# TTL.net
KiCad netlist of a schematic drawn in EAGLE
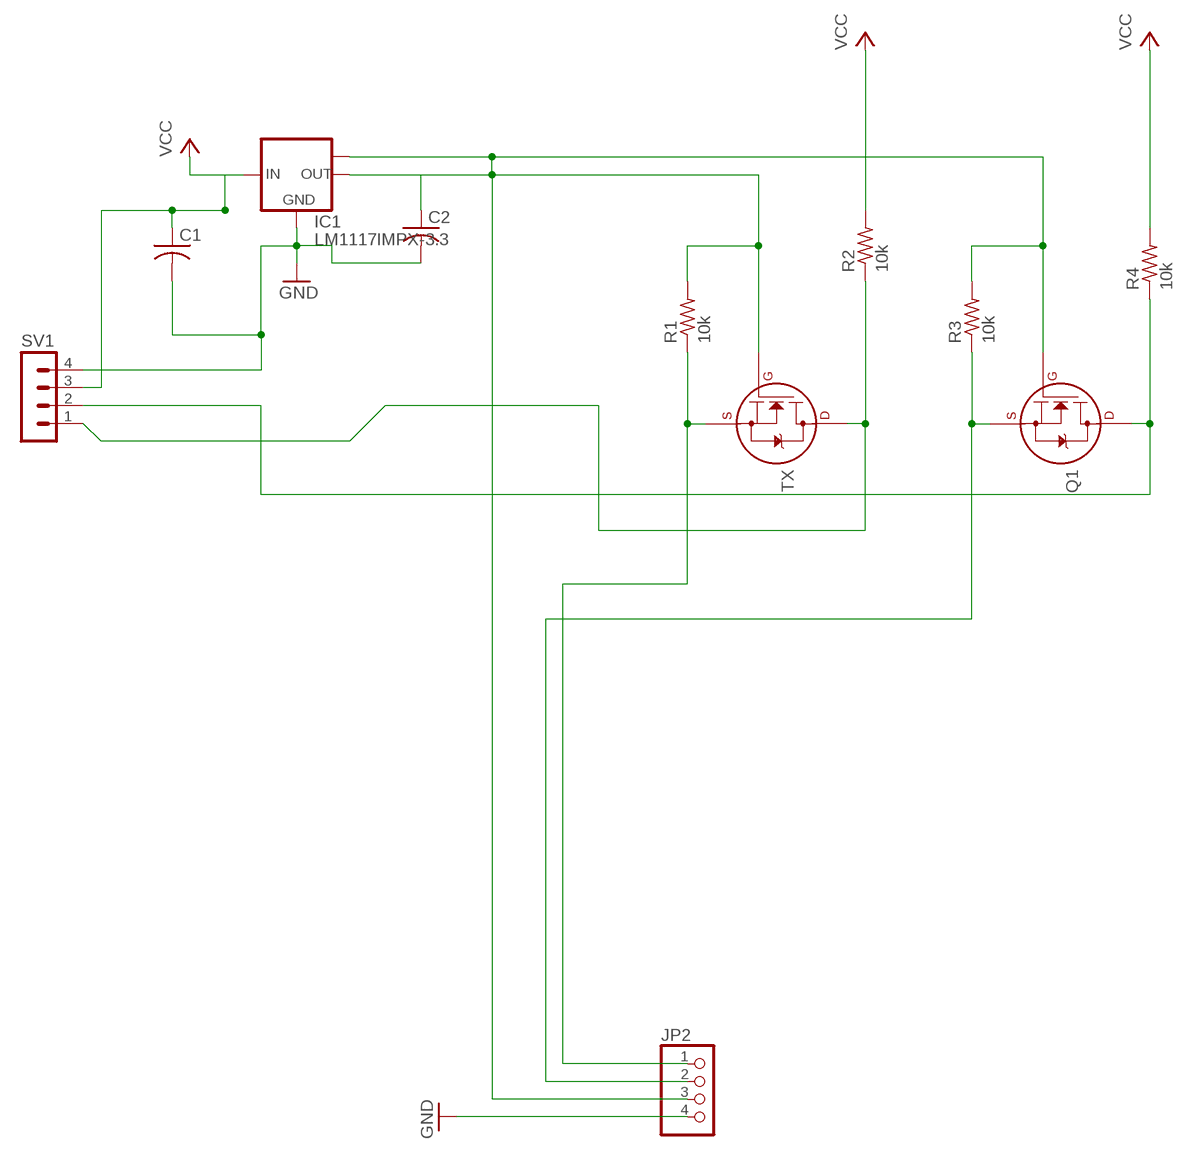
[diagram p0: schematic, sheet 1]

(export (version "E")
  (design (tool "Eeschema 10.0.6"))
  (components
    (comp (ref "C1")
      (value "C-USC0805")
      (footprint "eagle-import:C0805")
      (libsource (lib "eagle-import") (part "C-USC0805"))
    )
    (comp (ref "C2")
      (value "C-USC0805")
      (footprint "eagle-import:C0805")
      (libsource (lib "eagle-import") (part "C-USC0805"))
    )
    (comp (ref "IC1")
      (value "LM1117IMPX-3.3")
      (footprint "eagle-import:SOT223")
      (libsource (lib "eagle-import") (part "LM1117IMPX-3.3"))
    )
    (comp (ref "JP2")
      (value "PINHD-1X4")
      (footprint "eagle-import:1X04")
      (libsource (lib "eagle-import") (part "PINHD-1X4"))
    )
    (comp (ref "Q1")
      (value "2N7002_SOT23")
      (footprint "eagle-import:SOT-23")
      (libsource (lib "eagle-import") (part "2N700_SOT232"))
    )
    (comp (ref "R1")
      (value "10k")
      (footprint "eagle-import:M0805")
      (libsource (lib "eagle-import") (part "R-US_M0805"))
    )
    (comp (ref "R2")
      (value "10k")
      (footprint "eagle-import:M0805")
      (libsource (lib "eagle-import") (part "R-US_M0805"))
    )
    (comp (ref "R3")
      (value "10k")
      (footprint "eagle-import:M0805")
      (libsource (lib "eagle-import") (part "R-US_M0805"))
    )
    (comp (ref "R4")
      (value "10k")
      (footprint "eagle-import:M0805")
      (libsource (lib "eagle-import") (part "R-US_M0805"))
    )
    (comp (ref "SV1")
      (value "MA04-1")
      (footprint "eagle-import:MA04-1")
      (libsource (lib "eagle-import") (part "MA04-1"))
    )
    (comp (ref "TX")
      (value "2N7002_SOT23")
      (footprint "eagle-import:SOT-23")
      (libsource (lib "eagle-import") (part "2N700_SOT232"))
    )
  )
  (nets
    (net (code "1") (name "GND") (class "Default")
      (node (ref "C1") (pin "2") (pinfunction "2_2") (pintype "passive"))
      (node (ref "C2") (pin "2") (pinfunction "2_2") (pintype "passive"))
      (node (ref "IC1") (pin "1") (pinfunction "GND_1") (pintype "input"))
      (node (ref "JP2") (pin "4") (pinfunction "4_4") (pintype "passive"))
      (node (ref "SV1") (pin "4") (pinfunction "4_4") (pintype "passive"))
    )
    (net (code "2") (name "Net-(IC1-OUT)") (class "Default")
      (node (ref "C2") (pin "1") (pinfunction "1_1") (pintype "passive"))
      (node (ref "IC1") (pin "2") (pinfunction "OUT_2") (pintype "passive"))
      (node (ref "IC1") (pin "TAB") (pinfunction "OUT1_TAB") (pintype "passive"))
      (node (ref "JP2") (pin "3") (pinfunction "3_3") (pintype "passive"))
      (node (ref "Q1") (pin "1") (pinfunction "G_1") (pintype "tri_state"))
      (node (ref "R1") (pin "2") (pinfunction "2_2") (pintype "passive"))
      (node (ref "R3") (pin "2") (pinfunction "2_2") (pintype "passive"))
      (node (ref "TX") (pin "1") (pinfunction "G_1") (pintype "tri_state"))
    )
    (net (code "3") (name "Net-(Q1-D)") (class "Default")
      (node (ref "Q1") (pin "3") (pinfunction "D_3") (pintype "bidirectional"))
      (node (ref "R4") (pin "1") (pinfunction "1_1") (pintype "passive"))
      (node (ref "SV1") (pin "2") (pinfunction "2_2") (pintype "passive"))
    )
    (net (code "4") (name "Net-(Q1-S)") (class "Default")
      (node (ref "JP2") (pin "2") (pinfunction "2_2") (pintype "passive"))
      (node (ref "Q1") (pin "2") (pinfunction "S_2") (pintype "bidirectional"))
      (node (ref "R3") (pin "1") (pinfunction "1_1") (pintype "passive"))
    )
    (net (code "5") (name "Net-(TX-D)") (class "Default")
      (node (ref "R2") (pin "1") (pinfunction "1_1") (pintype "passive"))
      (node (ref "SV1") (pin "1") (pinfunction "1_1") (pintype "passive"))
      (node (ref "TX") (pin "3") (pinfunction "D_3") (pintype "bidirectional"))
    )
    (net (code "6") (name "Net-(TX-S)") (class "Default")
      (node (ref "JP2") (pin "1") (pinfunction "1_1") (pintype "passive"))
      (node (ref "R1") (pin "1") (pinfunction "1_1") (pintype "passive"))
      (node (ref "TX") (pin "2") (pinfunction "S_2") (pintype "bidirectional"))
    )
    (net (code "7") (name "VCC") (class "Default")
      (node (ref "C1") (pin "1") (pinfunction "1_1") (pintype "passive"))
      (node (ref "IC1") (pin "3") (pinfunction "IN_3") (pintype "input"))
      (node (ref "R2") (pin "2") (pinfunction "2_2") (pintype "passive"))
      (node (ref "R4") (pin "2") (pinfunction "2_2") (pintype "passive"))
      (node (ref "SV1") (pin "3") (pinfunction "3_3") (pintype "passive"))
    )
  )
)
